# Sensor-Board-v001.net
KiCad netlist of a schematic drawn in EAGLE
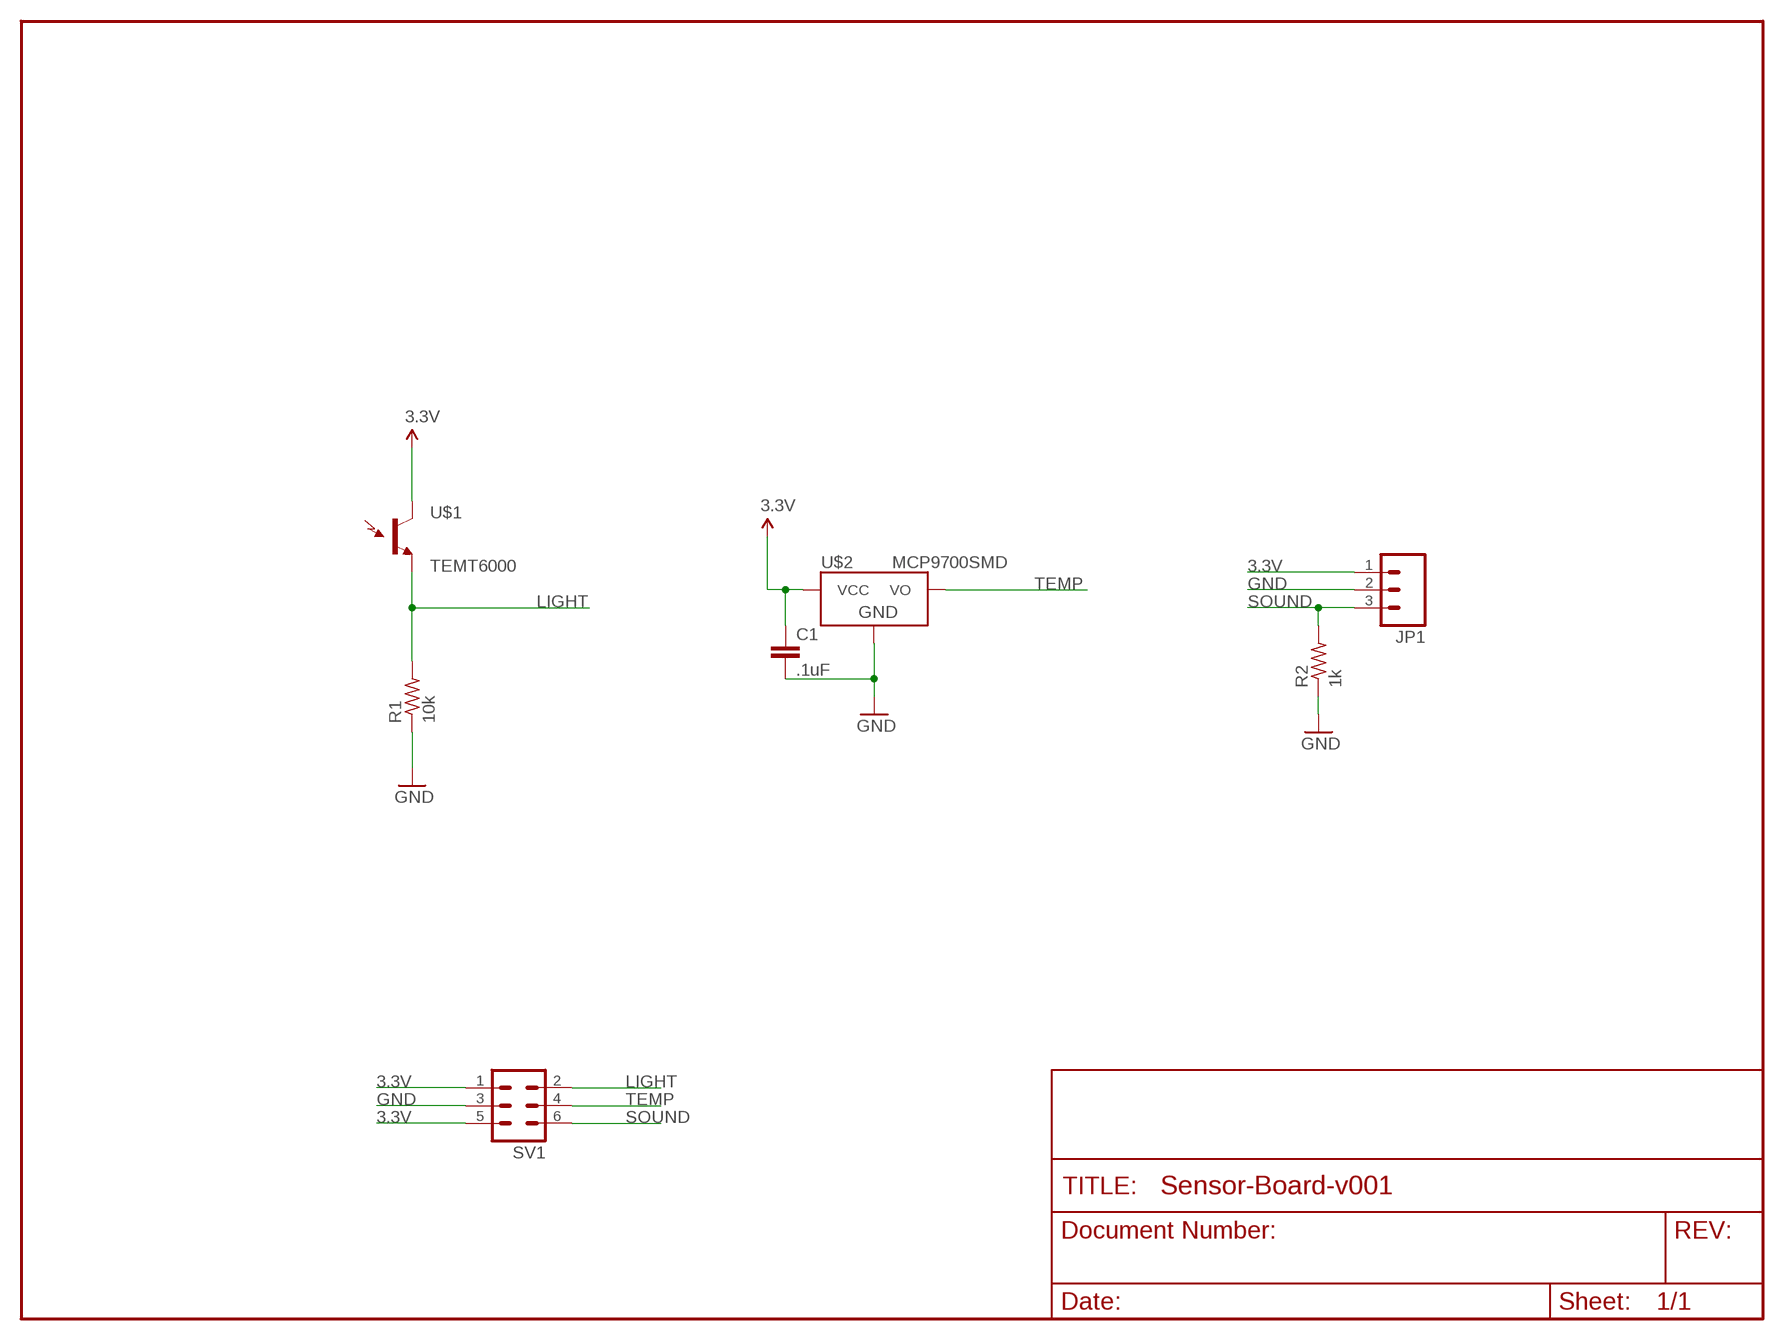
[diagram p0: schematic, sheet 1]

(export (version "E")
  (design (tool "Eeschema 10.0.6"))
  (components
    (comp (ref "C1")
      (value ".1uF")
      (footprint "eagle-import:0603-CAP")
      (libsource (lib "eagle-import") (part "CAP0603-CAP"))
    )
    (comp (ref "JP1")
      (value "M03PTH")
      (footprint "eagle-import:1X03")
      (libsource (lib "eagle-import") (part "M03PTH"))
    )
    (comp (ref "R1")
      (value "10k")
      (footprint "eagle-import:R0603")
      (libsource (lib "eagle-import") (part "R-US_R0603"))
    )
    (comp (ref "R2")
      (value "1k")
      (footprint "eagle-import:R0603")
      (libsource (lib "eagle-import") (part "R-US_R0603"))
    )
    (comp (ref "SV1")
      (value "ML6")
      (footprint "eagle-import:ML6")
      (libsource (lib "eagle-import") (part "ML6"))
    )
    (comp (ref "U$1")
      (value "TEMT6000")
      (footprint "eagle-import:TEMT6000-SEN")
      (libsource (lib "eagle-import") (part "TEMT6000"))
    )
    (comp (ref "U$2")
      (value "MCP9700SMD")
      (footprint "eagle-import:SOT23-3")
      (libsource (lib "eagle-import") (part "MCP9700SMD"))
    )
  )
  (nets
    (net (code "1") (name "/LIGHT") (class "Default")
      (node (ref "R1") (pin "2") (pinfunction "2_2") (pintype "passive"))
      (node (ref "SV1") (pin "2") (pinfunction "2_2") (pintype "passive"))
      (node (ref "U$1") (pin "EMITTER") (pinfunction "E1_EMITTER") (pintype "passive"))
    )
    (net (code "2") (name "/SOUND") (class "Default")
      (node (ref "JP1") (pin "3") (pinfunction "3_3") (pintype "passive"))
      (node (ref "R2") (pin "2") (pinfunction "2_2") (pintype "passive"))
      (node (ref "SV1") (pin "6") (pinfunction "6_6") (pintype "passive"))
    )
    (net (code "3") (name "/TEMP") (class "Default")
      (node (ref "SV1") (pin "4") (pinfunction "4_4") (pintype "passive"))
      (node (ref "U$2") (pin "2") (pinfunction "VO_2") (pintype "bidirectional"))
    )
    (net (code "4") (name "3.3V") (class "Default")
      (node (ref "C1") (pin "1") (pinfunction "1_1") (pintype "passive"))
      (node (ref "JP1") (pin "1") (pinfunction "1_1") (pintype "passive"))
      (node (ref "SV1") (pin "1") (pinfunction "1_1") (pintype "passive"))
      (node (ref "SV1") (pin "5") (pinfunction "5_5") (pintype "passive"))
      (node (ref "U$1") (pin "COLLECTOR") (pinfunction "C1_COLLECTOR") (pintype "passive"))
      (node (ref "U$2") (pin "1") (pinfunction "VCC_1") (pintype "bidirectional"))
    )
    (net (code "5") (name "GND") (class "Default")
      (node (ref "C1") (pin "2") (pinfunction "2_2") (pintype "passive"))
      (node (ref "JP1") (pin "2") (pinfunction "2_2") (pintype "passive"))
      (node (ref "R1") (pin "1") (pinfunction "1_1") (pintype "passive"))
      (node (ref "R2") (pin "1") (pinfunction "1_1") (pintype "passive"))
      (node (ref "SV1") (pin "3") (pinfunction "3_3") (pintype "passive"))
      (node (ref "U$2") (pin "3") (pinfunction "GND_3") (pintype "bidirectional"))
    )
  )
)
